# type-2_4_button.net
KiCad netlist of a schematic drawn in EAGLE
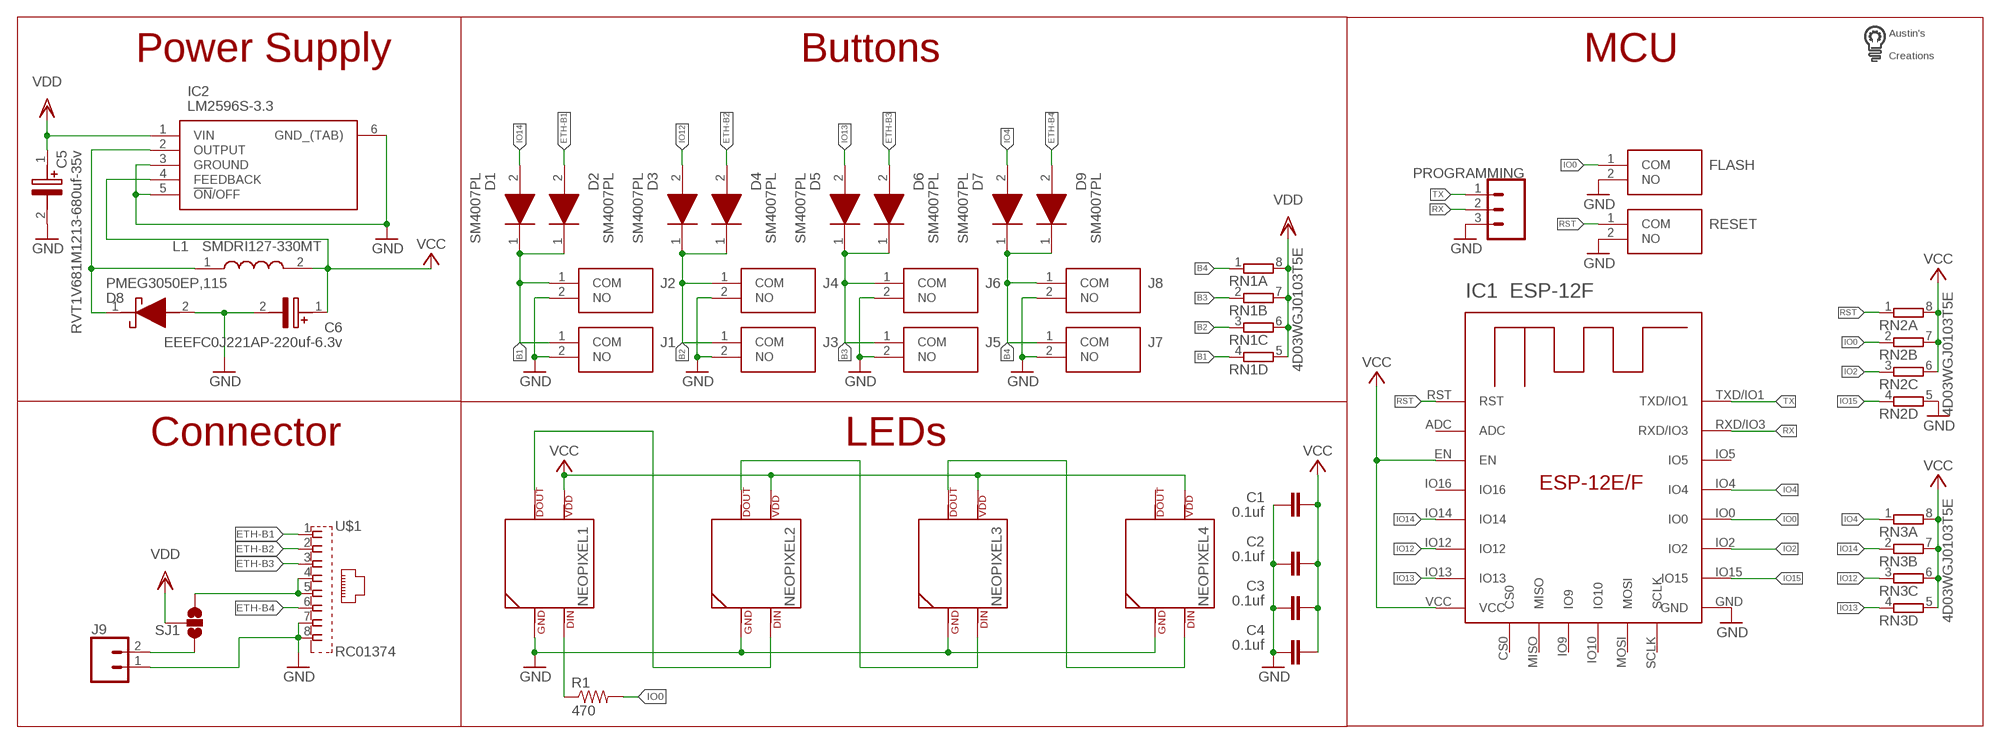
[diagram p0: schematic, sheet 1]

(export (version "E")
  (design (tool "Eeschema 10.0.6"))
  (components
    (comp (ref "C1")
      (value "0.1uf")
      (footprint "eagle-import:C0603")
      (libsource (lib "eagle-import") (part "C-EUC0603"))
    )
    (comp (ref "C2")
      (value "0.1uf")
      (footprint "eagle-import:C0603")
      (libsource (lib "eagle-import") (part "C-EUC0603"))
    )
    (comp (ref "C3")
      (value "0.1uf")
      (footprint "eagle-import:C0603")
      (libsource (lib "eagle-import") (part "C-EUC0603"))
    )
    (comp (ref "C4")
      (value "0.1uf")
      (footprint "eagle-import:C0603")
      (libsource (lib "eagle-import") (part "C-EUC0603"))
    )
    (comp (ref "C5")
      (value "RVT1V681M1213-680uf-35v")
      (footprint "eagle-import:CAPAE1350X1400N")
      (fields
        (field (name "MANUFACTURER_PART_NUMBER") "EEE-HD1V681AQ")
        (field (name "MOUSER_PART_NUMBER") "667-EEE-HD1V681AQ")
      )
      (libsource (lib "eagle-import") (part "EEE-HD1V681AQ"))
    )
    (comp (ref "C6")
      (value "EEEFC0J221AP-220uf-6.3v")
      (footprint "eagle-import:CAPAE830X650N")
      (fields (field (name "MANUFACTURER_PART_NUMBER") "EEEFC0J221AP"))
      (libsource (lib "eagle-import") (part "EEEFC0J221AP"))
    )
    (comp (ref "D1")
      (value "SM4007PL")
      (footprint "eagle-import:SODFL3718X125N")
      (libsource (lib "eagle-import") (part "SM4007PL"))
    )
    (comp (ref "D2")
      (value "SM4007PL")
      (footprint "eagle-import:SODFL3718X125N")
      (libsource (lib "eagle-import") (part "SM4007PL"))
    )
    (comp (ref "D3")
      (value "SM4007PL")
      (footprint "eagle-import:SODFL3718X125N")
      (libsource (lib "eagle-import") (part "SM4007PL"))
    )
    (comp (ref "D4")
      (value "SM4007PL")
      (footprint "eagle-import:SODFL3718X125N")
      (libsource (lib "eagle-import") (part "SM4007PL"))
    )
    (comp (ref "D5")
      (value "SM4007PL")
      (footprint "eagle-import:SODFL3718X125N")
      (libsource (lib "eagle-import") (part "SM4007PL"))
    )
    (comp (ref "D6")
      (value "SM4007PL")
      (footprint "eagle-import:SODFL3718X125N")
      (libsource (lib "eagle-import") (part "SM4007PL"))
    )
    (comp (ref "D7")
      (value "SM4007PL")
      (footprint "eagle-import:SODFL3718X125N")
      (libsource (lib "eagle-import") (part "SM4007PL"))
    )
    (comp (ref "D8")
      (value "PMEG3050EP,115")
      (footprint "eagle-import:PMEG3050EP115")
      (fields (field (name "MOUSER_PART_NUMBER") "771-PMEG3050EP115"))
      (libsource (lib "eagle-import") (part "PMEG3050EP,115"))
    )
    (comp (ref "D9")
      (value "SM4007PL")
      (footprint "eagle-import:SODFL3718X125N")
      (libsource (lib "eagle-import") (part "SM4007PL"))
    )
    (comp (ref "FLASH")
      (value "PTS636_SM25F_SMTR_LFS")
      (footprint "eagle-import:PTS636SM25FSMTRLFS")
      (fields
        (field (name "ARROW_PART_NUMBER") "PTS636 SM25F SMTR LFS")
        (field (name "MOUSER_PART_NUMBER") "611-PTS636SM25FSMTRL")
      )
      (libsource (lib "eagle-import") (part "PTS636_SM25F_SMTR_LFS"))
    )
    (comp (ref "IC1")
      (value "ESP-12F")
      (footprint "eagle-import:ESP-12E")
      (libsource (lib "eagle-import") (part "ESP-12E/F"))
    )
    (comp (ref "IC2")
      (value "LM2596S-3.3")
      (footprint "eagle-import:TO170P1435X465-6N")
      (fields
        (field (name "MANUFACTURER_PART_NUMBER") "LM2596S-3.3/NOPB")
        (field (name "MOUSER_PART_NUMBER") "926-LM2596S-3.3/NOPB")
      )
      (libsource (lib "eagle-import") (part "LM2596S-3.3_NOPB"))
    )
    (comp (ref "J1")
      (value "PTS636_SM25F_SMTR_LFS")
      (footprint "eagle-import:PTS636SM25FSMTRLFS")
      (fields
        (field (name "ARROW_PART_NUMBER") "PTS636 SM25F SMTR LFS")
        (field (name "MOUSER_PART_NUMBER") "611-PTS636SM25FSMTRL")
      )
      (libsource (lib "eagle-import") (part "PTS636_SM25F_SMTR_LFS"))
    )
    (comp (ref "J2")
      (value "PTS636_SM25F_SMTR_LFS")
      (footprint "eagle-import:PTS636SM25FSMTRLFS")
      (fields
        (field (name "ARROW_PART_NUMBER") "PTS636 SM25F SMTR LFS")
        (field (name "MOUSER_PART_NUMBER") "611-PTS636SM25FSMTRL")
      )
      (libsource (lib "eagle-import") (part "PTS636_SM25F_SMTR_LFS"))
    )
    (comp (ref "J3")
      (value "PTS636_SM25F_SMTR_LFS")
      (footprint "eagle-import:PTS636SM25FSMTRLFS")
      (fields
        (field (name "ARROW_PART_NUMBER") "PTS636 SM25F SMTR LFS")
        (field (name "MOUSER_PART_NUMBER") "611-PTS636SM25FSMTRL")
      )
      (libsource (lib "eagle-import") (part "PTS636_SM25F_SMTR_LFS"))
    )
    (comp (ref "J4")
      (value "PTS636_SM25F_SMTR_LFS")
      (footprint "eagle-import:PTS636SM25FSMTRLFS")
      (fields
        (field (name "ARROW_PART_NUMBER") "PTS636 SM25F SMTR LFS")
        (field (name "MOUSER_PART_NUMBER") "611-PTS636SM25FSMTRL")
      )
      (libsource (lib "eagle-import") (part "PTS636_SM25F_SMTR_LFS"))
    )
    (comp (ref "J5")
      (value "PTS636_SM25F_SMTR_LFS")
      (footprint "eagle-import:PTS636SM25FSMTRLFS")
      (fields
        (field (name "ARROW_PART_NUMBER") "PTS636 SM25F SMTR LFS")
        (field (name "MOUSER_PART_NUMBER") "611-PTS636SM25FSMTRL")
      )
      (libsource (lib "eagle-import") (part "PTS636_SM25F_SMTR_LFS"))
    )
    (comp (ref "J6")
      (value "PTS636_SM25F_SMTR_LFS")
      (footprint "eagle-import:PTS636SM25FSMTRLFS")
      (fields
        (field (name "ARROW_PART_NUMBER") "PTS636 SM25F SMTR LFS")
        (field (name "MOUSER_PART_NUMBER") "611-PTS636SM25FSMTRL")
      )
      (libsource (lib "eagle-import") (part "PTS636_SM25F_SMTR_LFS"))
    )
    (comp (ref "J7")
      (value "PTS636_SM25F_SMTR_LFS")
      (footprint "eagle-import:PTS636SM25FSMTRLFS")
      (fields
        (field (name "ARROW_PART_NUMBER") "PTS636 SM25F SMTR LFS")
        (field (name "MOUSER_PART_NUMBER") "611-PTS636SM25FSMTRL")
      )
      (libsource (lib "eagle-import") (part "PTS636_SM25F_SMTR_LFS"))
    )
    (comp (ref "J8")
      (value "PTS636_SM25F_SMTR_LFS")
      (footprint "eagle-import:PTS636SM25FSMTRLFS")
      (fields
        (field (name "ARROW_PART_NUMBER") "PTS636 SM25F SMTR LFS")
        (field (name "MOUSER_PART_NUMBER") "611-PTS636SM25FSMTRL")
      )
      (libsource (lib "eagle-import") (part "PTS636_SM25F_SMTR_LFS"))
    )
    (comp (ref "J9")
      (value "CONN_025MM")
      (footprint "eagle-import:SCREWTERMINAL-5MM-2")
      (libsource (lib "eagle-import") (part "CONN_025MM"))
    )
    (comp (ref "L1")
      (value "SMDRI127-330MT")
      (footprint "eagle-import:INDPM120120X800N")
      (fields
        (field (name "MANUFACTURER_PART_NUMBER") "CDRH127/LDNP-330MC")
        (field (name "MOUSER_PART_NUMBER") "851-CDRH127LDNP330MC")
      )
      (libsource (lib "eagle-import") (part "CDRH127_LDNP-330MC"))
    )
    (comp (ref "NEOPIXEL1")
      (value "SK6812NEOPIXEL5050")
      (footprint "eagle-import:SK6812")
      (libsource (lib "eagle-import") (part "SK68125050NEOPIXEL"))
    )
    (comp (ref "NEOPIXEL2")
      (value "SK6812NEOPIXEL5050")
      (footprint "eagle-import:SK6812")
      (libsource (lib "eagle-import") (part "SK68125050NEOPIXEL"))
    )
    (comp (ref "NEOPIXEL3")
      (value "SK6812NEOPIXEL5050")
      (footprint "eagle-import:SK6812")
      (libsource (lib "eagle-import") (part "SK68125050NEOPIXEL"))
    )
    (comp (ref "NEOPIXEL4")
      (value "SK6812NEOPIXEL5050")
      (footprint "eagle-import:SK6812")
      (libsource (lib "eagle-import") (part "SK68125050NEOPIXEL"))
    )
    (comp (ref "PROGRAMMING")
      (value "455-1750-1-ND")
      (footprint "eagle-import:1X03")
      (libsource (lib "eagle-import") (part "CONN_03"))
    )
    (comp (ref "R1")
      (value "470")
      (footprint "eagle-import:R0603")
      (libsource (lib "eagle-import") (part "R-US_R0603"))
    )
    (comp (ref "RESET")
      (value "PTS636_SM25F_SMTR_LFS")
      (footprint "eagle-import:PTS636SM25FSMTRLFS")
      (fields
        (field (name "ARROW_PART_NUMBER") "PTS636 SM25F SMTR LFS")
        (field (name "MOUSER_PART_NUMBER") "611-PTS636SM25FSMTRL")
      )
      (libsource (lib "eagle-import") (part "PTS636_SM25F_SMTR_LFS"))
    )
    (comp (ref "RN1")
      (value "4R-N0603-ARC")
      (footprint "eagle-import:0603-ARC")
      (libsource (lib "eagle-import") (part "4R-N0603-ARC"))
    )
    (comp (ref "RN2")
      (value "4R-N0603-ARC")
      (footprint "eagle-import:0603-ARC")
      (libsource (lib "eagle-import") (part "4R-N0603-ARC"))
    )
    (comp (ref "RN3")
      (value "4R-N0603-ARC")
      (footprint "eagle-import:0603-ARC")
      (libsource (lib "eagle-import") (part "4R-N0603-ARC"))
    )
    (comp (ref "SJ1")
      (value "SOLDERJUMPER_2WAYPASTE1&2")
      (footprint "eagle-import:SJ_3_PASTE1&2")
      (libsource (lib "eagle-import") (part "SOLDERJUMPER_2WAYPASTE1&2"))
    )
    (comp (ref "U$1")
      (value "RC01374")
      (footprint "eagle-import:RC01374")
      (libsource (lib "eagle-import") (part "RC01374"))
    )
    (comp (ref "U$2")
      (value "LOGO")
      (footprint "eagle-import:LOGO")
      (libsource (lib "eagle-import") (part "LOGO"))
    )
  )
  (nets
    (net (code "1") (name "B1") (class "Default")
      (node (ref "D1") (pin "1") (pinfunction "K_1") (pintype "bidirectional"))
      (node (ref "D2") (pin "1") (pinfunction "K_1") (pintype "bidirectional"))
      (node (ref "J1") (pin "1") (pinfunction "COM_1") (pintype "bidirectional"))
      (node (ref "J2") (pin "1") (pinfunction "COM_1") (pintype "bidirectional"))
      (node (ref "RN1") (pin "4") (pinfunction "1_4") (pintype "passive"))
    )
    (net (code "2") (name "B2") (class "Default")
      (node (ref "D3") (pin "1") (pinfunction "K_1") (pintype "bidirectional"))
      (node (ref "D4") (pin "1") (pinfunction "K_1") (pintype "bidirectional"))
      (node (ref "J3") (pin "1") (pinfunction "COM_1") (pintype "bidirectional"))
      (node (ref "J4") (pin "1") (pinfunction "COM_1") (pintype "bidirectional"))
      (node (ref "RN1") (pin "3") (pinfunction "1_3") (pintype "passive"))
    )
    (net (code "3") (name "B3") (class "Default")
      (node (ref "D5") (pin "1") (pinfunction "K_1") (pintype "bidirectional"))
      (node (ref "D6") (pin "1") (pinfunction "K_1") (pintype "bidirectional"))
      (node (ref "J5") (pin "1") (pinfunction "COM_1") (pintype "bidirectional"))
      (node (ref "J6") (pin "1") (pinfunction "COM_1") (pintype "bidirectional"))
      (node (ref "RN1") (pin "2") (pinfunction "1_2") (pintype "passive"))
    )
    (net (code "4") (name "B4") (class "Default")
      (node (ref "D7") (pin "1") (pinfunction "K_1") (pintype "bidirectional"))
      (node (ref "D9") (pin "1") (pinfunction "K_1") (pintype "bidirectional"))
      (node (ref "J7") (pin "1") (pinfunction "COM_1") (pintype "bidirectional"))
      (node (ref "J8") (pin "1") (pinfunction "COM_1") (pintype "bidirectional"))
      (node (ref "RN1") (pin "1") (pinfunction "1_1") (pintype "passive"))
    )
    (net (code "5") (name "ETH-B1") (class "Default")
      (node (ref "D2") (pin "2") (pinfunction "A_2") (pintype "bidirectional"))
      (node (ref "U$1") (pin "1") (pinfunction "1_1") (pintype "passive"))
    )
    (net (code "6") (name "ETH-B2") (class "Default")
      (node (ref "D4") (pin "2") (pinfunction "A_2") (pintype "bidirectional"))
      (node (ref "U$1") (pin "2") (pinfunction "2_2") (pintype "passive"))
    )
    (net (code "7") (name "ETH-B3") (class "Default")
      (node (ref "D6") (pin "2") (pinfunction "A_2") (pintype "bidirectional"))
      (node (ref "U$1") (pin "3") (pinfunction "3_3") (pintype "passive"))
    )
    (net (code "8") (name "ETH-B4") (class "Default")
      (node (ref "D9") (pin "2") (pinfunction "A_2") (pintype "bidirectional"))
      (node (ref "U$1") (pin "6") (pinfunction "6_6") (pintype "passive"))
    )
    (net (code "9") (name "GND") (class "Default")
      (node (ref "C1") (pin "1") (pinfunction "1_1") (pintype "passive"))
      (node (ref "C2") (pin "1") (pinfunction "1_1") (pintype "passive"))
      (node (ref "C3") (pin "1") (pinfunction "1_1") (pintype "passive"))
      (node (ref "C4") (pin "1") (pinfunction "1_1") (pintype "passive"))
      (node (ref "C5") (pin "2") (pinfunction "-_2") (pintype "bidirectional"))
      (node (ref "C6") (pin "2") (pinfunction "-_2") (pintype "bidirectional"))
      (node (ref "D8") (pin "2") (pinfunction "A_2") (pintype "bidirectional"))
      (node (ref "FLASH") (pin "2") (pinfunction "NO_2") (pintype "bidirectional"))
      (node (ref "IC1") (pin "GND") (pinfunction "GND_GND") (pintype "power_in"))
      (node (ref "IC2") (pin "3") (pinfunction "GROUND_3") (pintype "bidirectional"))
      (node (ref "IC2") (pin "5") (pinfunction "~{ON}/OFF_5") (pintype "bidirectional"))
      (node (ref "IC2") (pin "6") (pinfunction "GND_(TAB)_6") (pintype "power_in"))
      (node (ref "J1") (pin "2") (pinfunction "NO_2") (pintype "bidirectional"))
      (node (ref "J2") (pin "2") (pinfunction "NO_2") (pintype "bidirectional"))
      (node (ref "J3") (pin "2") (pinfunction "NO_2") (pintype "bidirectional"))
      (node (ref "J4") (pin "2") (pinfunction "NO_2") (pintype "bidirectional"))
      (node (ref "J5") (pin "2") (pinfunction "NO_2") (pintype "bidirectional"))
      (node (ref "J6") (pin "2") (pinfunction "NO_2") (pintype "bidirectional"))
      (node (ref "J7") (pin "2") (pinfunction "NO_2") (pintype "bidirectional"))
      (node (ref "J8") (pin "2") (pinfunction "NO_2") (pintype "bidirectional"))
      (node (ref "J9") (pin "1") (pinfunction "1_1") (pintype "passive"))
      (node (ref "NEOPIXEL1") (pin "3") (pinfunction "GND_3") (pintype "bidirectional"))
      (node (ref "NEOPIXEL2") (pin "3") (pinfunction "GND_3") (pintype "bidirectional"))
      (node (ref "NEOPIXEL3") (pin "3") (pinfunction "GND_3") (pintype "bidirectional"))
      (node (ref "NEOPIXEL4") (pin "3") (pinfunction "GND_3") (pintype "bidirectional"))
      (node (ref "PROGRAMMING") (pin "3") (pinfunction "3_3") (pintype "passive"))
      (node (ref "RESET") (pin "2") (pinfunction "NO_2") (pintype "bidirectional"))
      (node (ref "RN2") (pin "5") (pinfunction "2_5") (pintype "passive"))
      (node (ref "U$1") (pin "7") (pinfunction "7_7") (pintype "passive"))
      (node (ref "U$1") (pin "8") (pinfunction "8_8") (pintype "passive"))
    )
    (net (code "10") (name "IO0") (class "Default")
      (node (ref "FLASH") (pin "1") (pinfunction "COM_1") (pintype "bidirectional"))
      (node (ref "IC1") (pin "IO0") (pinfunction "IO0_IO0") (pintype "bidirectional"))
      (node (ref "R1") (pin "2") (pinfunction "2_2") (pintype "passive"))
      (node (ref "RN2") (pin "2") (pinfunction "1_2") (pintype "passive"))
    )
    (net (code "11") (name "IO2") (class "Default")
      (node (ref "IC1") (pin "IO2") (pinfunction "IO2_IO2") (pintype "bidirectional"))
      (node (ref "RN2") (pin "3") (pinfunction "1_3") (pintype "passive"))
    )
    (net (code "12") (name "IO4") (class "Default")
      (node (ref "D7") (pin "2") (pinfunction "A_2") (pintype "bidirectional"))
      (node (ref "IC1") (pin "IO4") (pinfunction "IO4_IO4") (pintype "bidirectional"))
      (node (ref "RN3") (pin "1") (pinfunction "1_1") (pintype "passive"))
    )
    (net (code "13") (name "IO12") (class "Default")
      (node (ref "D3") (pin "2") (pinfunction "A_2") (pintype "bidirectional"))
      (node (ref "IC1") (pin "IO12") (pinfunction "IO12_IO12") (pintype "bidirectional"))
      (node (ref "RN3") (pin "3") (pinfunction "1_3") (pintype "passive"))
    )
    (net (code "14") (name "IO13") (class "Default")
      (node (ref "D5") (pin "2") (pinfunction "A_2") (pintype "bidirectional"))
      (node (ref "IC1") (pin "IO13") (pinfunction "IO13_IO13") (pintype "bidirectional"))
      (node (ref "RN3") (pin "4") (pinfunction "1_4") (pintype "passive"))
    )
    (net (code "15") (name "IO14") (class "Default")
      (node (ref "D1") (pin "2") (pinfunction "A_2") (pintype "bidirectional"))
      (node (ref "IC1") (pin "IO14") (pinfunction "IO14_IO14") (pintype "bidirectional"))
      (node (ref "RN3") (pin "2") (pinfunction "1_2") (pintype "passive"))
    )
    (net (code "16") (name "IO15") (class "Default")
      (node (ref "IC1") (pin "IO15") (pinfunction "IO15_IO15") (pintype "bidirectional"))
      (node (ref "RN2") (pin "4") (pinfunction "1_4") (pintype "passive"))
    )
    (net (code "17") (name "Net-(D8-K)") (class "Default")
      (node (ref "D8") (pin "1") (pinfunction "K_1") (pintype "bidirectional"))
      (node (ref "IC2") (pin "2") (pinfunction "OUTPUT_2") (pintype "output"))
      (node (ref "L1") (pin "1") (pinfunction "1_1") (pintype "bidirectional"))
    )
    (net (code "18") (name "Net-(J9-Pad2)") (class "Default")
      (node (ref "J9") (pin "2") (pinfunction "2_2") (pintype "passive"))
      (node (ref "SJ1") (pin "3") (pinfunction "3_3") (pintype "passive"))
    )
    (net (code "19") (name "Net-(NEOPIXEL1-DIN)") (class "Default")
      (node (ref "NEOPIXEL1") (pin "4") (pinfunction "DIN_4") (pintype "bidirectional"))
      (node (ref "R1") (pin "1") (pinfunction "1_1") (pintype "passive"))
    )
    (net (code "20") (name "Net-(NEOPIXEL1-DOUT)") (class "Default")
      (node (ref "NEOPIXEL1") (pin "2") (pinfunction "DOUT_2") (pintype "bidirectional"))
      (node (ref "NEOPIXEL2") (pin "4") (pinfunction "DIN_4") (pintype "bidirectional"))
    )
    (net (code "21") (name "Net-(NEOPIXEL2-DOUT)") (class "Default")
      (node (ref "NEOPIXEL2") (pin "2") (pinfunction "DOUT_2") (pintype "bidirectional"))
      (node (ref "NEOPIXEL3") (pin "4") (pinfunction "DIN_4") (pintype "bidirectional"))
    )
    (net (code "22") (name "Net-(NEOPIXEL3-DOUT)") (class "Default")
      (node (ref "NEOPIXEL3") (pin "2") (pinfunction "DOUT_2") (pintype "bidirectional"))
      (node (ref "NEOPIXEL4") (pin "4") (pinfunction "DIN_4") (pintype "bidirectional"))
    )
    (net (code "23") (name "Net-(SJ1-Pad1)") (class "Default")
      (node (ref "SJ1") (pin "1") (pinfunction "1_1") (pintype "passive"))
      (node (ref "U$1") (pin "4") (pinfunction "4_4") (pintype "passive"))
      (node (ref "U$1") (pin "5") (pinfunction "5_5") (pintype "passive"))
    )
    (net (code "24") (name "RST") (class "Default")
      (node (ref "IC1") (pin "RST") (pinfunction "RST_RST") (pintype "input"))
      (node (ref "RESET") (pin "1") (pinfunction "COM_1") (pintype "bidirectional"))
      (node (ref "RN2") (pin "1") (pinfunction "1_1") (pintype "passive"))
    )
    (net (code "25") (name "RX") (class "Default")
      (node (ref "IC1") (pin "RXD/IO3") (pinfunction "RXD/IO3_RXD/IO3") (pintype "bidirectional"))
      (node (ref "PROGRAMMING") (pin "2") (pinfunction "2_2") (pintype "passive"))
    )
    (net (code "26") (name "TX") (class "Default")
      (node (ref "IC1") (pin "TXD/IO1") (pinfunction "TXD/IO1_TXD/IO1") (pintype "bidirectional"))
      (node (ref "PROGRAMMING") (pin "1") (pinfunction "1_1") (pintype "passive"))
    )
    (net (code "27") (name "VCC") (class "Default")
      (node (ref "C1") (pin "2") (pinfunction "2_2") (pintype "passive"))
      (node (ref "C2") (pin "2") (pinfunction "2_2") (pintype "passive"))
      (node (ref "C3") (pin "2") (pinfunction "2_2") (pintype "passive"))
      (node (ref "C4") (pin "2") (pinfunction "2_2") (pintype "passive"))
      (node (ref "C6") (pin "1") (pinfunction "+_1") (pintype "bidirectional"))
      (node (ref "IC1") (pin "EN") (pinfunction "EN_EN") (pintype "bidirectional"))
      (node (ref "IC1") (pin "VCC") (pinfunction "VCC_VCC") (pintype "power_in"))
      (node (ref "IC2") (pin "4") (pinfunction "FEEDBACK_4") (pintype "bidirectional"))
      (node (ref "L1") (pin "2") (pinfunction "2_2") (pintype "bidirectional"))
      (node (ref "NEOPIXEL1") (pin "1") (pinfunction "VDD_1") (pintype "bidirectional"))
      (node (ref "NEOPIXEL2") (pin "1") (pinfunction "VDD_1") (pintype "bidirectional"))
      (node (ref "NEOPIXEL3") (pin "1") (pinfunction "VDD_1") (pintype "bidirectional"))
      (node (ref "NEOPIXEL4") (pin "1") (pinfunction "VDD_1") (pintype "bidirectional"))
      (node (ref "RN2") (pin "6") (pinfunction "2_6") (pintype "passive"))
      (node (ref "RN2") (pin "7") (pinfunction "2_7") (pintype "passive"))
      (node (ref "RN2") (pin "8") (pinfunction "2_8") (pintype "passive"))
      (node (ref "RN3") (pin "5") (pinfunction "2_5") (pintype "passive"))
      (node (ref "RN3") (pin "6") (pinfunction "2_6") (pintype "passive"))
      (node (ref "RN3") (pin "7") (pinfunction "2_7") (pintype "passive"))
      (node (ref "RN3") (pin "8") (pinfunction "2_8") (pintype "passive"))
    )
    (net (code "28") (name "VDD") (class "Default")
      (node (ref "C5") (pin "1") (pinfunction "+_1") (pintype "bidirectional"))
      (node (ref "IC2") (pin "1") (pinfunction "VIN_1") (pintype "input"))
      (node (ref "RN1") (pin "5") (pinfunction "2_5") (pintype "passive"))
      (node (ref "RN1") (pin "6") (pinfunction "2_6") (pintype "passive"))
      (node (ref "RN1") (pin "7") (pinfunction "2_7") (pintype "passive"))
      (node (ref "RN1") (pin "8") (pinfunction "2_8") (pintype "passive"))
      (node (ref "SJ1") (pin "2") (pinfunction "2_2") (pintype "passive"))
    )
    (net (code "29") (name "unconnected-(IC1-PadADC)") (class "Default")
      (node (ref "IC1") (pin "ADC") (pinfunction "ADC_ADC") (pintype "bidirectional"))
    )
    (net (code "30") (name "unconnected-(IC1-PadCS0)") (class "Default")
      (node (ref "IC1") (pin "CS0") (pinfunction "CS0_CS0") (pintype "bidirectional"))
    )
    (net (code "31") (name "unconnected-(IC1-PadIO5)") (class "Default")
      (node (ref "IC1") (pin "IO5") (pinfunction "IO5_IO5") (pintype "bidirectional"))
    )
    (net (code "32") (name "unconnected-(IC1-PadIO9)") (class "Default")
      (node (ref "IC1") (pin "IO9") (pinfunction "IO9_IO9") (pintype "bidirectional"))
    )
    (net (code "33") (name "unconnected-(IC1-PadIO10)") (class "Default")
      (node (ref "IC1") (pin "IO10") (pinfunction "IO10_IO10") (pintype "bidirectional"))
    )
    (net (code "34") (name "unconnected-(IC1-PadIO16)") (class "Default")
      (node (ref "IC1") (pin "IO16") (pinfunction "IO16_IO16") (pintype "bidirectional"))
    )
    (net (code "35") (name "unconnected-(IC1-PadMISO)") (class "Default")
      (node (ref "IC1") (pin "MISO") (pinfunction "MISO_MISO") (pintype "bidirectional"))
    )
    (net (code "36") (name "unconnected-(IC1-PadMOSI)") (class "Default")
      (node (ref "IC1") (pin "MOSI") (pinfunction "MOSI_MOSI") (pintype "bidirectional"))
    )
    (net (code "37") (name "unconnected-(IC1-PadSCLK)") (class "Default")
      (node (ref "IC1") (pin "SCLK") (pinfunction "SCLK_SCLK") (pintype "bidirectional"))
    )
    (net (code "38") (name "unconnected-(NEOPIXEL4-DOUT-Pad2)") (class "Default")
      (node (ref "NEOPIXEL4") (pin "2") (pinfunction "DOUT_2") (pintype "bidirectional"))
    )
  )
)
